# atuador_geral.net
KiCad netlist of a schematic drawn in Altium Designer
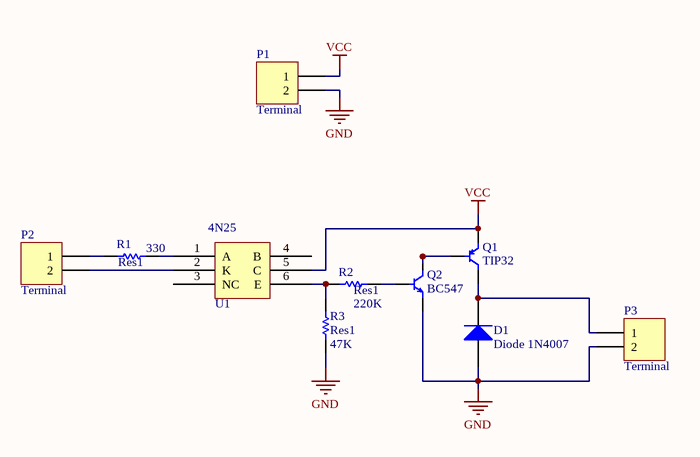
[diagram p0: atuador_geral.SchDoc]

(export (version "E")
  (design (tool "Eeschema 10.0.6"))
  (components
    (comp (ref "D1")
      (value "Diode 1N4007")
      (footprint "DO-41")
      (description "1 Amp General Purpose Rectifier")
      (fields (field (name "PUBLISHER") "Altium Limited"))
      (libsource (lib "Miscellaneous Devices") (part "Diode 1N4007"))
    )
    (comp (ref "P1")
      (value "Terminal")
      (footprint "KRE_2")
      (description "Terminal Block 1x2")
      (libsource (lib "GPDSE") (part "KRE_2"))
    )
    (comp (ref "P2")
      (value "Terminal")
      (footprint "KRE_2")
      (description "Terminal Block 1x2")
      (libsource (lib "GPDSE") (part "KRE_2"))
    )
    (comp (ref "P3")
      (value "Terminal")
      (footprint "KRE_2")
      (description "Terminal Block 1x2")
      (libsource (lib "") (part "KRE_2_1"))
    )
    (comp (ref "Q1")
      (value "TIP32")
      (footprint "TO-220/BCE")
      (description "PNP Epitaxial Silicon Transistor")
      (fields (field (name "COMPLEMENTARY PART") "TIP31"))
      (libsource (lib "GPDSE") (part "TIP32"))
    )
    (comp (ref "Q2")
      (value "BC547")
      (footprint "TO-92/CBE")
      (description "NPN Epitaxial Silicon Transistor")
      (fields (field (name "COMPLEMENTARY PART") "BC557"))
      (libsource (lib "GPDSE") (part "BC547"))
    )
    (comp (ref "R1")
      (value "Res1")
      (footprint "AXIAL-0.3")
      (description "Resistor")
      (fields (field (name "ALTIUM_VALUE") "330") (field (name "PUBLISHER") "Altium Limited"))
      (libsource (lib "Miscellaneous Devices") (part "Res1"))
    )
    (comp (ref "R2")
      (value "Res1")
      (footprint "AXIAL-0.3")
      (description "Resistor")
      (fields (field (name "ALTIUM_VALUE") "220K") (field (name "PUBLISHER") "Altium Limited"))
      (libsource (lib "Miscellaneous Devices") (part "Res1"))
    )
    (comp (ref "R3")
      (value "Res1")
      (footprint "AXIAL-0.3")
      (description "Resistor")
      (fields (field (name "ALTIUM_VALUE") "47K") (field (name "PUBLISHER") "Altium Limited"))
      (libsource (lib "Miscellaneous Devices") (part "Res1"))
    )
    (comp (ref "U1") (value "4N25") (footprint "4N25") (libsource (lib "Schlib1") (part "4N25")))
  )
  (nets
    (net (code "1") (name "GND") (class "Default")
      (node (ref "D1") (pin "1") (pinfunction "A_1") (pintype "passive"))
      (node (ref "P1") (pin "2") (pinfunction "2_2") (pintype "passive"))
      (node (ref "P3") (pin "2") (pinfunction "2_2") (pintype "passive"))
      (node (ref "Q2") (pin "E") (pinfunction "E_E") (pintype "passive"))
      (node (ref "R3") (pin "1") (pinfunction "1_1") (pintype "passive"))
    )
    (net (code "2") (name "Net-(D1-K)") (class "Default")
      (node (ref "D1") (pin "2") (pinfunction "K_2") (pintype "passive"))
      (node (ref "P3") (pin "1") (pinfunction "1_1") (pintype "passive"))
      (node (ref "Q1") (pin "C") (pinfunction "C_C") (pintype "passive"))
    )
    (net (code "3") (name "Net-(P2-Pad1)") (class "Default")
      (node (ref "P2") (pin "1") (pinfunction "1_1") (pintype "passive"))
      (node (ref "R1") (pin "1") (pinfunction "1_1") (pintype "passive"))
    )
    (net (code "4") (name "Net-(Q1-PadB)") (class "Default")
      (node (ref "Q1") (pin "B") (pinfunction "B_B") (pintype "passive"))
      (node (ref "Q2") (pin "C") (pinfunction "C_C") (pintype "passive"))
    )
    (net (code "5") (name "Net-(Q2-PadB)") (class "Default")
      (node (ref "Q2") (pin "B") (pinfunction "B_B") (pintype "passive"))
      (node (ref "R2") (pin "2") (pinfunction "2_2") (pintype "passive"))
    )
    (net (code "6") (name "Net-(U1-A)") (class "Default")
      (node (ref "R1") (pin "2") (pinfunction "2_2") (pintype "passive"))
      (node (ref "U1") (pin "1") (pinfunction "A_1") (pintype "passive"))
    )
    (net (code "7") (name "Net-(U1-E)") (class "Default")
      (node (ref "R2") (pin "1") (pinfunction "1_1") (pintype "passive"))
      (node (ref "R3") (pin "2") (pinfunction "2_2") (pintype "passive"))
      (node (ref "U1") (pin "6") (pinfunction "E_6") (pintype "passive"))
    )
    (net (code "8") (name "Net-(U1-K)") (class "Default")
      (node (ref "P2") (pin "2") (pinfunction "2_2") (pintype "passive"))
      (node (ref "U1") (pin "2") (pinfunction "K_2") (pintype "passive"))
    )
    (net (code "9") (name "VCC") (class "Default")
      (node (ref "P1") (pin "1") (pinfunction "1_1") (pintype "passive"))
      (node (ref "Q1") (pin "E") (pinfunction "E_E") (pintype "passive"))
      (node (ref "U1") (pin "5") (pinfunction "C_5") (pintype "passive"))
    )
    (net (code "10") (name "unconnected-(U1-B-Pad4)") (class "Default")
      (node (ref "U1") (pin "4") (pinfunction "B_4") (pintype "passive"))
    )
    (net (code "11") (name "unconnected-(U1-NC-Pad3)") (class "Default")
      (node (ref "U1") (pin "3") (pinfunction "NC_3") (pintype "passive"))
    )
  )
)
